# Flyback_Converter_New.net
KiCad netlist of a schematic drawn in Altium Designer
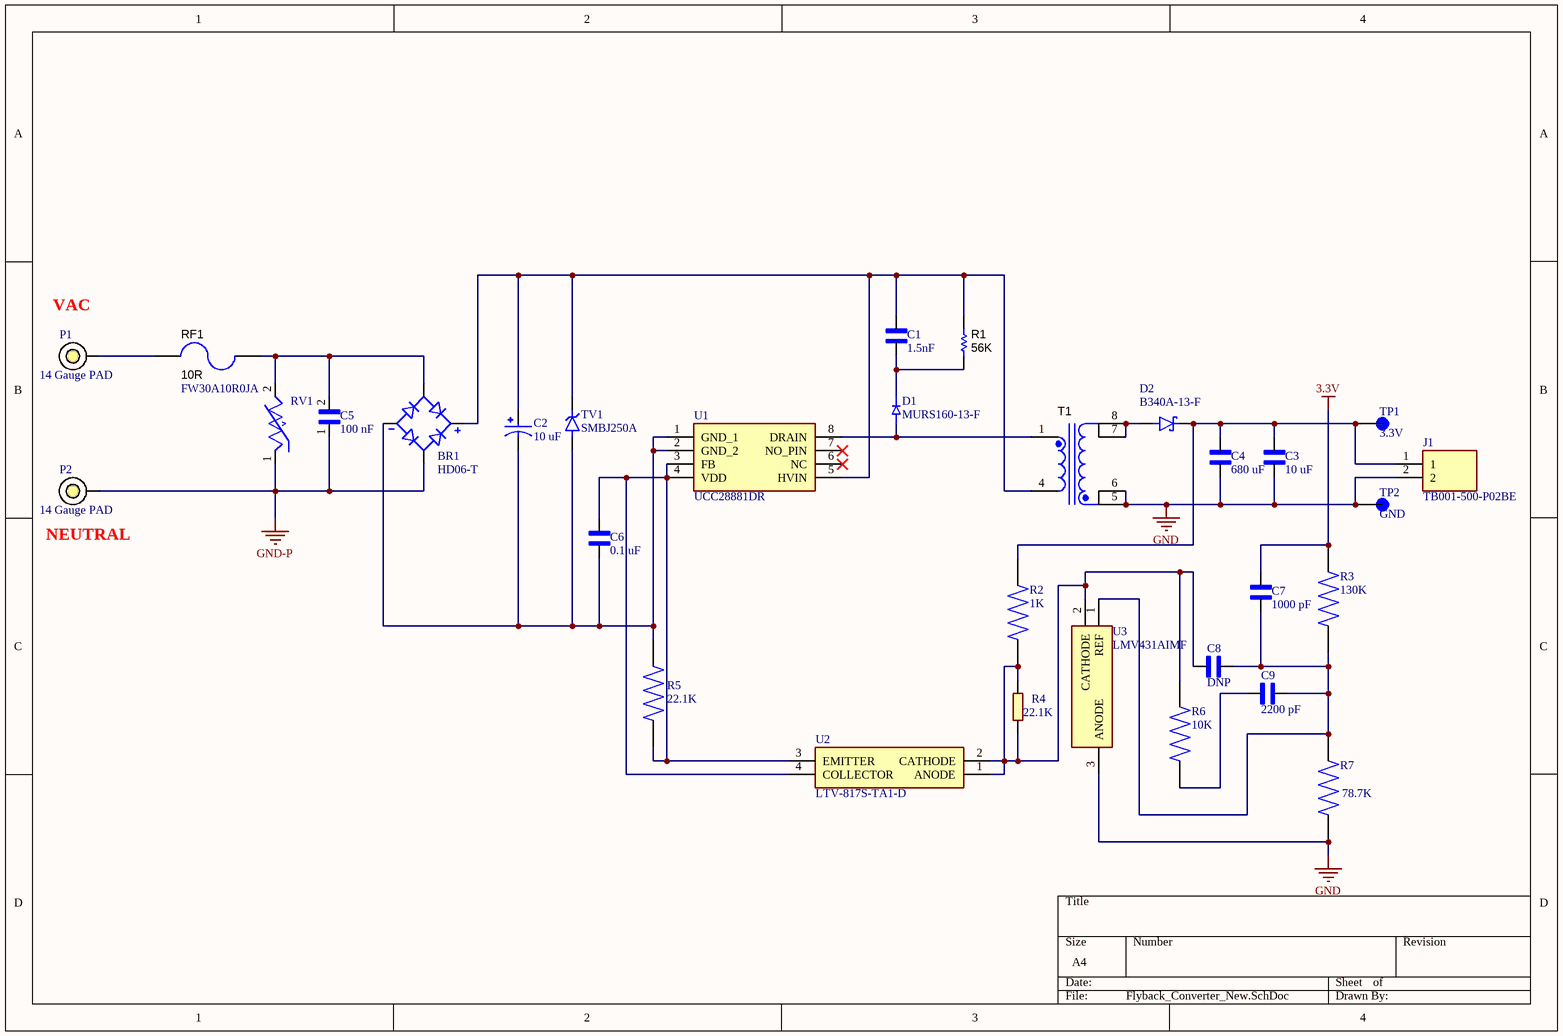
[diagram p0: Flyback_Converter_New.SchDoc]

(export (version "E")
  (design (tool "Eeschema 10.0.6"))
  (components
    (comp (ref "BR1")
      (value "HD06-T")
      (footprint "DIOB_HD06-T")
      (description "KÃ¶prÃ¼ DoÄŸrultucu Tek FazlÄ± Standart 600 V YÃ¼zey MontajlÄ± 4-MiniDIP")
      (fields (field (name "MF") "Diodes Inc."))
      (libsource (lib "HD06-T") (part "HD06-T"))
    )
    (comp (ref "C1")
      (value "1.5nF")
      (footprint "CAPC1608X87N")
      (description "Cap Ceramic 0.0015uF 10V X7R 10% SMD 0603 125Â°C Paper T/R")
      (fields (field (name "MF") "KEMET") (field (name "MP") "C0603C152K8RACTU"))
      (libsource (lib "C1_FLY") (part "C0603C152K8RACTU"))
    )
    (comp (ref "C2")
      (value "10 uF")
      (footprint "450BXW10MEFR10X16 - duplicate")
      (description "10ÂµF 450V Aluminum Electrolytic Capacitors Radial, Can 10000 Hrs @ 105Â°C")
      (fields (field (name "MP") "450BXW10MEFR10X16") (field (name "MF") "Rubycon"))
      (libsource (lib "C2_FLY") (part "450BXW10MEFR10X16"))
    )
    (comp (ref "C3")
      (value "10 uF")
      (footprint "CAPC1608X120N")
      (description "SMD capacitor X5R(EIA) with capacitance 10uF Tol.20%. Rated voltage 25Vdc 85C")
      (fields (field (name "MF") "Murata") (field (name "MP") "ZRB18AR61E106ME01L"))
      (libsource (lib "C3_FLY") (part "ZRB18AR61E106ME01L"))
    )
    (comp (ref "C4")
      (value "680 uF")
      (footprint "CAPPM7343X310N")
      (description "680 ÂµF Molded Tantalum Capacitors 6.3 V 2917 (7343 Metric) 23mOhm")
      (fields (field (name "MF") "AVX") (field (name "MP") "TPME687M006R0023"))
      (libsource (lib "C4_FLY") (part "TPME687M006R0023"))
    )
    (comp (ref "C5")
      (value "100 nF")
      (footprint "CAPRR1500W60L1750T500H1200")
      (fields (field (name "MP") "ECQUAAF104SA") (field (name "MF") "Panasonic"))
      (libsource (lib "C5_FLY") (part "ECQUAAF104SA"))
    )
    (comp (ref "C6")
      (value "0.1 uF")
      (footprint "CAPC1608X90N")
      (description "0.1 ÂµF Â±10% 16V Ceramic Capacitor X7R 0603 (1608 Metric)")
      (fields (field (name "MF") "KEMET") (field (name "MP") "C0603C104K4RAC"))
      (libsource (lib "C6_FLY") (part "C0603C104K4RAC"))
    )
    (comp (ref "C7")
      (value "1000 pF")
      (footprint "CAPC1608X90N")
      (description "0603 1000 pF 50 V Â±2% Tolerance C0G Multilayer Ceramic Capacitor")
      (fields (field (name "MF") "AVX") (field (name "MP") "06035A102GAT2A"))
      (libsource (lib "C7") (part "06035A102GAT2A"))
    )
    (comp (ref "C8")
      (value "DNP")
      (footprint "CAPC1608X95")
      (description "1 ÂµF Â±10% 16V Ceramic Capacitor X7R 0603 (1608 Metric)")
      (fields (field (name "MF") "TDK") (field (name "MP") "C1608X7R1C105K"))
      (libsource (lib "C8") (part "C1608X7R1C105K"))
    )
    (comp (ref "C9")
      (value "2200 pF")
      (footprint "CAPC1608X87N")
      (description "Cap Cer 2200pf 50v 5% X7r 0603")
      (fields (field (name "MF") "KEMET") (field (name "MP") "C0603S222J5RACTU"))
      (libsource (lib "C9") (part "C0603S222J5RACTU"))
    )
    (comp (ref "D1")
      (value "MURS160-13-F")
      (footprint "MURS160-13-F")
      (description "Diode Switching 600V 1A 2Pin SMB ¦ Diodes Inc MURS160-13-F")
      (fields (field (name "MF") "Diodes Inc."))
      (libsource (lib "D1_FLY") (part "MURS160-13-F"))
    )
    (comp (ref "D2")
      (value "B340A-13-F")
      (footprint "DIOM5226X240N")
      (description "Schottky Diode 3A 40V 0.5Vf SMA ¦ Diodes Inc B340A-13-F")
      (fields (field (name "MF") "Diodes Inc."))
      (libsource (lib "D2_FLY") (part "B340A-13-F"))
    )
    (comp (ref "J1")
      (value "TB001-500-P02BE")
      (footprint "CUI_TB001-500-P02BE")
      (description "2~24 Poles, Screw Type, Horizontal, 5.0 Pitch, 22~12 (AWG), Terminal Block Connector")
      (fields (field (name "MF") "Same Sky"))
      (libsource (lib "J1_FLYBACK") (part "TB001-500-P02BE"))
    )
    (comp (ref "P1")
      (value "14 Gauge PAD")
      (footprint "PAD_1.6MM_WIRE")
      (description "5.2MM WIRE PAD")
      (fields (field (name "MANUFACTURER") "NA"))
      (libsource (lib "WinLogic") (part "14 Gauge PAD"))
    )
    (comp (ref "P2")
      (value "14 Gauge PAD")
      (footprint "PAD_1.6MM_WIRE")
      (description "5.2MM WIRE PAD")
      (fields (field (name "MANUFACTURER") "NA"))
      (libsource (lib "WinLogic") (part "14 Gauge PAD"))
    )
    (comp (ref "R1")
      (value "56K")
      (footprint "RESAD2950W85L1150D450")
      (description "RES 56K OHM 2W 5% AXIAL")
      (fields
        (field (name "MANUFACTURER") "Vishay Beyschlag/Draloric/BC Components")
        (field (name "MANUFACTURER PART NUMBER") "PR02000205602JR200")
      )
      (libsource (lib "Resistor_1206") (part "CRCW1206100KJNEA"))
    )
    (comp (ref "R2")
      (value "1K")
      (footprint "RESC1608X55N")
      (fields (field (name "MF") "Bourns Electronics") (field (name "MP") "CR0603FX1001ELF"))
      (libsource (lib "R2_FLY") (part "CR0603-FX-1001ELF"))
    )
    (comp (ref "R3")
      (value "130K")
      (footprint "RES_ERJS03F1303V")
      (description "Res Thick Film 0603 130K Ohm 1% 1/10W Â±100ppm/Â°C Molded SMD SMD Punched Carrier T/R")
      (fields (field (name "MF") "Panasonic") (field (name "MP") "ERJS03F1303V"))
      (libsource (lib "R3") (part "ERJS03F1303V"))
    )
    (comp (ref "R4")
      (value "22.1K")
      (footprint "0603")
      (description "22.1 Ohms Â±1% 0.1W, 1/10W Chip Resistor 0603 (1608 Metric) Moisture Resistant Thick Film")
      (fields (field (name "MF") "Yageo") (field (name "MP") "RC0603FR-0722R1L"))
      (libsource (lib "R4_FLY") (part "RC0603FR-0722R1L"))
    )
    (comp (ref "R5")
      (value "22.1K")
      (footprint "RES_ERJ3EKF2212V")
      (fields (field (name "MF") "Panasonic") (field (name "MP") "ERJ-3EKF2212V"))
      (libsource (lib "R5_FLY") (part "ERJ3EKF2212V"))
    )
    (comp (ref "R6")
      (value "10K")
      (footprint "RESC1608X55N")
      (fields (field (name "MP") "RK73G1JTTD1002F"))
      (libsource (lib "R6") (part "RK73G1JTTD1002F"))
    )
    (comp (ref "R7")
      (value "78.7K")
      (footprint "RES_ERJ3EKF7872V")
      (description "Res Thick Film 0603 78.7K Ohm 1% 1/10W 100ppm/C Molded SMD SMD Punched Carrier T/R")
      (fields (field (name "MF") "Panasonic") (field (name "MP") "ERJ-3EKF7872V"))
      (libsource (lib "R7") (part "ERJ3EKF7872V"))
    )
    (comp (ref "RF1")
      (value "10R")
      (footprint "FKN3WSJT-73-10R")
      (description "Res Fusible Wirewound 10 Ohm 5% 3W ±350ppm/°C Conformal Axial Ammo Pack")
      (fields
        (field (name "MANUFACTURER") "Bourns")
        (field (name "TOLERANCE") "5%")
        (field (name "MANUFACTURER PART NUMBER") "FW30A10R0JA")
      )
      (libsource (lib "WinLogic") (part "FW30A10R0JA"))
    )
    (comp (ref "RV1")
      (value "~")
      (footprint "B72210P2271K101")
      (fields (field (name "MF") "TDK ELECTRONICS") (field (name "MP") "B72210P2271K101"))
      (libsource (lib "RV1_FLY") (part "B72210P2271K101"))
    )
    (comp (ref "T1")
      (value "CUSTOM")
      (footprint "TRANSFORMER_EFD20/10/7")
      (description "Core Type: EFD20/10/7  Core Material: N49  Turns Ratio(Nps): 69:4")
      (libsource (lib "WinLogic") (part "TRANSFORMER"))
    )
    (comp (ref "TP1")
      (value "3.3V")
      (footprint "KEYSTONE_5269")
      (description "TEST POINT (PURPLE) - MINIATURE")
      (fields (field (name "MF") "Keystone Electronics") (field (name "MP") "5269"))
      (libsource (lib "TEST_POINT_PURPLE") (part "5269"))
    )
    (comp (ref "TP2")
      (value "GND")
      (footprint "KEYSTONE_5269")
      (description "TEST POINT (PURPLE) - MINIATURE")
      (fields (field (name "MF") "Keystone Electronics") (field (name "MP") "5269"))
      (libsource (lib "TEST_POINT_PURPLE") (part "5269"))
    )
    (comp (ref "TV1")
      (value "SMBJ250A")
      (footprint "D0-214AA_SMB")
      (description "405V Clamp 1.5A Ipp Tvs Diode Surface Mount DO-214AA (SMBJ)")
      (fields (field (name "MF") "Littelfuse"))
      (libsource (lib "TV1") (part "SMBJ250A"))
    )
    (comp (ref "U1")
      (value "UCC28881DR")
      (footprint "SOIC127P600X175-8N")
      (description "700-V Lowest Quiescent Current Off-Line Switcher")
      (fields (field (name "MOUSER PART NUMBER") "595-UCC28881DR"))
      (libsource (lib "UCC28881DR") (part "UCC28881DR"))
    )
    (comp (ref "U2")
      (value "LTV-817S-TA1-D")
      (footprint "LTV-817S_LTO")
      (fields (field (name "MOUSER PART NUMBER") "859-LTV-817S-TA1-D"))
      (libsource (lib "LTV-817S-TA1-D") (part "LTV-817S-TA1-D"))
    )
    (comp (ref "U3")
      (value "LMV431AIMF")
      (footprint "SOT-23")
      (description "Voltage References NRND, alternate is LMV431AIMF/NOPB")
      (fields (field (name "MOUSER PART NUMBER") "926-LMV431AIMF"))
      (libsource (lib "LMV431AIMF") (part "LMV431AIMF"))
    )
  )
  (nets
    (net (code "1") (name "3.3V") (class "Default")
      (node (ref "C7") (pin "2") (pinfunction "2_2") (pintype "passive"))
      (node (ref "R3") (pin "2") (pinfunction "2_2") (pintype "passive"))
    )
    (net (code "2") (name "GND") (class "Default")
      (node (ref "C3") (pin "1") (pinfunction "1_1") (pintype "passive"))
      (node (ref "C4") (pin "2") (pinfunction "2_2") (pintype "passive"))
      (node (ref "J1") (pin "2") (pinfunction "2_2") (pintype "passive"))
      (node (ref "R7") (pin "1") (pinfunction "1_1") (pintype "passive"))
      (node (ref "T1") (pin "5") (pinfunction "5_5") (pintype "passive"))
      (node (ref "T1") (pin "6") (pinfunction "6_6") (pintype "passive"))
      (node (ref "TP2") (pin "TP") (pinfunction "TP_TP") (pintype "passive"))
      (node (ref "U3") (pin "3") (pinfunction "ANODE_3") (pintype "passive"))
    )
    (net (code "3") (name "GND-P") (class "Default")
      (node (ref "BR1") (pin "AC1") (pinfunction "AC1_AC1") (pintype "passive"))
      (node (ref "C5") (pin "1") (pinfunction "1_1") (pintype "passive"))
      (node (ref "P2") (pin "1") (pinfunction "1_1") (pintype "passive"))
      (node (ref "RV1") (pin "1") (pinfunction "1_1") (pintype "passive"))
    )
    (net (code "4") (name "Net-(BR1-PadAC2)") (class "Default")
      (node (ref "BR1") (pin "AC2") (pinfunction "AC2_AC2") (pintype "passive"))
      (node (ref "C5") (pin "2") (pinfunction "2_2") (pintype "passive"))
      (node (ref "RF1") (pin "1") (pinfunction "1_1") (pintype "passive"))
      (node (ref "RV1") (pin "2") (pinfunction "2_2") (pintype "passive"))
    )
    (net (code "5") (name "Net-(C3-Pad2)") (class "Default")
      (node (ref "C3") (pin "2") (pinfunction "2_2") (pintype "passive"))
      (node (ref "C4") (pin "1") (pinfunction "1_1") (pintype "passive"))
      (node (ref "D2") (pin "C") (pinfunction "C_C") (pintype "passive"))
      (node (ref "J1") (pin "1") (pinfunction "1_1") (pintype "passive"))
      (node (ref "R2") (pin "2") (pinfunction "2_2") (pintype "passive"))
      (node (ref "TP1") (pin "TP") (pinfunction "TP_TP") (pintype "passive"))
    )
    (net (code "6") (name "Net-(C9-Pad1)") (class "Default")
      (node (ref "C9") (pin "1") (pinfunction "1_1") (pintype "passive"))
      (node (ref "R6") (pin "2") (pinfunction "2_2") (pintype "passive"))
    )
    (net (code "7") (name "Net-(D1-A)") (class "Default")
      (node (ref "D1") (pin "2") (pinfunction "A_2") (pintype "passive"))
      (node (ref "T1") (pin "1") (pinfunction "1_1") (pintype "passive"))
      (node (ref "U1") (pin "8") (pinfunction "DRAIN_8") (pintype "passive"))
    )
    (net (code "8") (name "Net-(D1-C)") (class "Default")
      (node (ref "C1") (pin "1") (pinfunction "1_1") (pintype "passive"))
      (node (ref "D1") (pin "1") (pinfunction "C_1") (pintype "passive"))
      (node (ref "R1") (pin "1") (pinfunction "1_1") (pintype "passive"))
    )
    (net (code "9") (name "Net-(D2-PadA)") (class "Default")
      (node (ref "D2") (pin "A") (pinfunction "A_A") (pintype "passive"))
      (node (ref "T1") (pin "7") (pinfunction "7_7") (pintype "passive"))
      (node (ref "T1") (pin "8") (pinfunction "8_8") (pintype "passive"))
    )
    (net (code "10") (name "Net-(P1-Pad1)") (class "Default")
      (node (ref "P1") (pin "1") (pinfunction "1_1") (pintype "passive"))
      (node (ref "RF1") (pin "2") (pinfunction "2_2") (pintype "passive"))
    )
    (net (code "11") (name "Net-(TV1-A)") (class "Default")
      (node (ref "BR1") (pin "NEG") (pinfunction "NEG_NEG") (pintype "passive"))
      (node (ref "C2") (pin "N") (pinfunction "N_N") (pintype "passive"))
      (node (ref "C6") (pin "1") (pinfunction "1_1") (pintype "passive"))
      (node (ref "R5") (pin "2") (pinfunction "2_2") (pintype "passive"))
      (node (ref "TV1") (pin "2") (pinfunction "A_2") (pintype "passive"))
      (node (ref "U1") (pin "1") (pinfunction "GND_1_1") (pintype "passive"))
      (node (ref "U1") (pin "2") (pinfunction "GND_2_2") (pintype "passive"))
    )
    (net (code "12") (name "Net-(TV1-K)") (class "Default")
      (node (ref "BR1") (pin "POS") (pinfunction "POS_POS") (pintype "passive"))
      (node (ref "C1") (pin "2") (pinfunction "2_2") (pintype "passive"))
      (node (ref "C2") (pin "P") (pinfunction "P_P") (pintype "passive"))
      (node (ref "R1") (pin "2") (pinfunction "2_2") (pintype "passive"))
      (node (ref "T1") (pin "4") (pinfunction "4_4") (pintype "passive"))
      (node (ref "TV1") (pin "1") (pinfunction "K_1") (pintype "passive"))
      (node (ref "U1") (pin "5") (pinfunction "HVIN_5") (pintype "power_in"))
    )
    (net (code "13") (name "Net-(U1-FB)") (class "Default")
      (node (ref "C6") (pin "2") (pinfunction "2_2") (pintype "passive"))
      (node (ref "R5") (pin "1") (pinfunction "1_1") (pintype "passive"))
      (node (ref "U1") (pin "3") (pinfunction "FB_3") (pintype "passive"))
      (node (ref "U1") (pin "4") (pinfunction "VDD_4") (pintype "power_in"))
      (node (ref "U2") (pin "3") (pinfunction "EMITTER_3") (pintype "passive"))
      (node (ref "U2") (pin "4") (pinfunction "COLLECTOR_4") (pintype "passive"))
    )
    (net (code "14") (name "Net-(U2-ANODE)") (class "Default")
      (node (ref "C8") (pin "2") (pinfunction "2_2") (pintype "passive"))
      (node (ref "R2") (pin "1") (pinfunction "1_1") (pintype "passive"))
      (node (ref "R4") (pin "1") (pinfunction "1_1") (pintype "passive"))
      (node (ref "R4") (pin "2") (pinfunction "2_2") (pintype "passive"))
      (node (ref "R6") (pin "1") (pinfunction "1_1") (pintype "passive"))
      (node (ref "U2") (pin "1") (pinfunction "ANODE_1") (pintype "passive"))
      (node (ref "U2") (pin "2") (pinfunction "CATHODE_2") (pintype "passive"))
      (node (ref "U3") (pin "2") (pinfunction "CATHODE_2") (pintype "passive"))
    )
    (net (code "15") (name "Net-(U3-REF)") (class "Default")
      (node (ref "C7") (pin "1") (pinfunction "1_1") (pintype "passive"))
      (node (ref "C8") (pin "1") (pinfunction "1_1") (pintype "passive"))
      (node (ref "C9") (pin "2") (pinfunction "2_2") (pintype "passive"))
      (node (ref "R3") (pin "1") (pinfunction "1_1") (pintype "passive"))
      (node (ref "R7") (pin "2") (pinfunction "2_2") (pintype "passive"))
      (node (ref "U3") (pin "1") (pinfunction "REF_1") (pintype "passive"))
    )
    (net (code "16") (name "unconnected-(U1-NC-Pad6)") (class "Default")
      (node (ref "U1") (pin "6") (pinfunction "NC_6") (pintype "passive+no_connect"))
    )
    (net (code "17") (name "unconnected-(U1-NO_PIN-Pad7)") (class "Default")
      (node (ref "U1") (pin "7") (pinfunction "NO_PIN_7") (pintype "passive+no_connect"))
    )
  )
)
